# car.net
KiCad netlist of a schematic drawn in Altium Designer
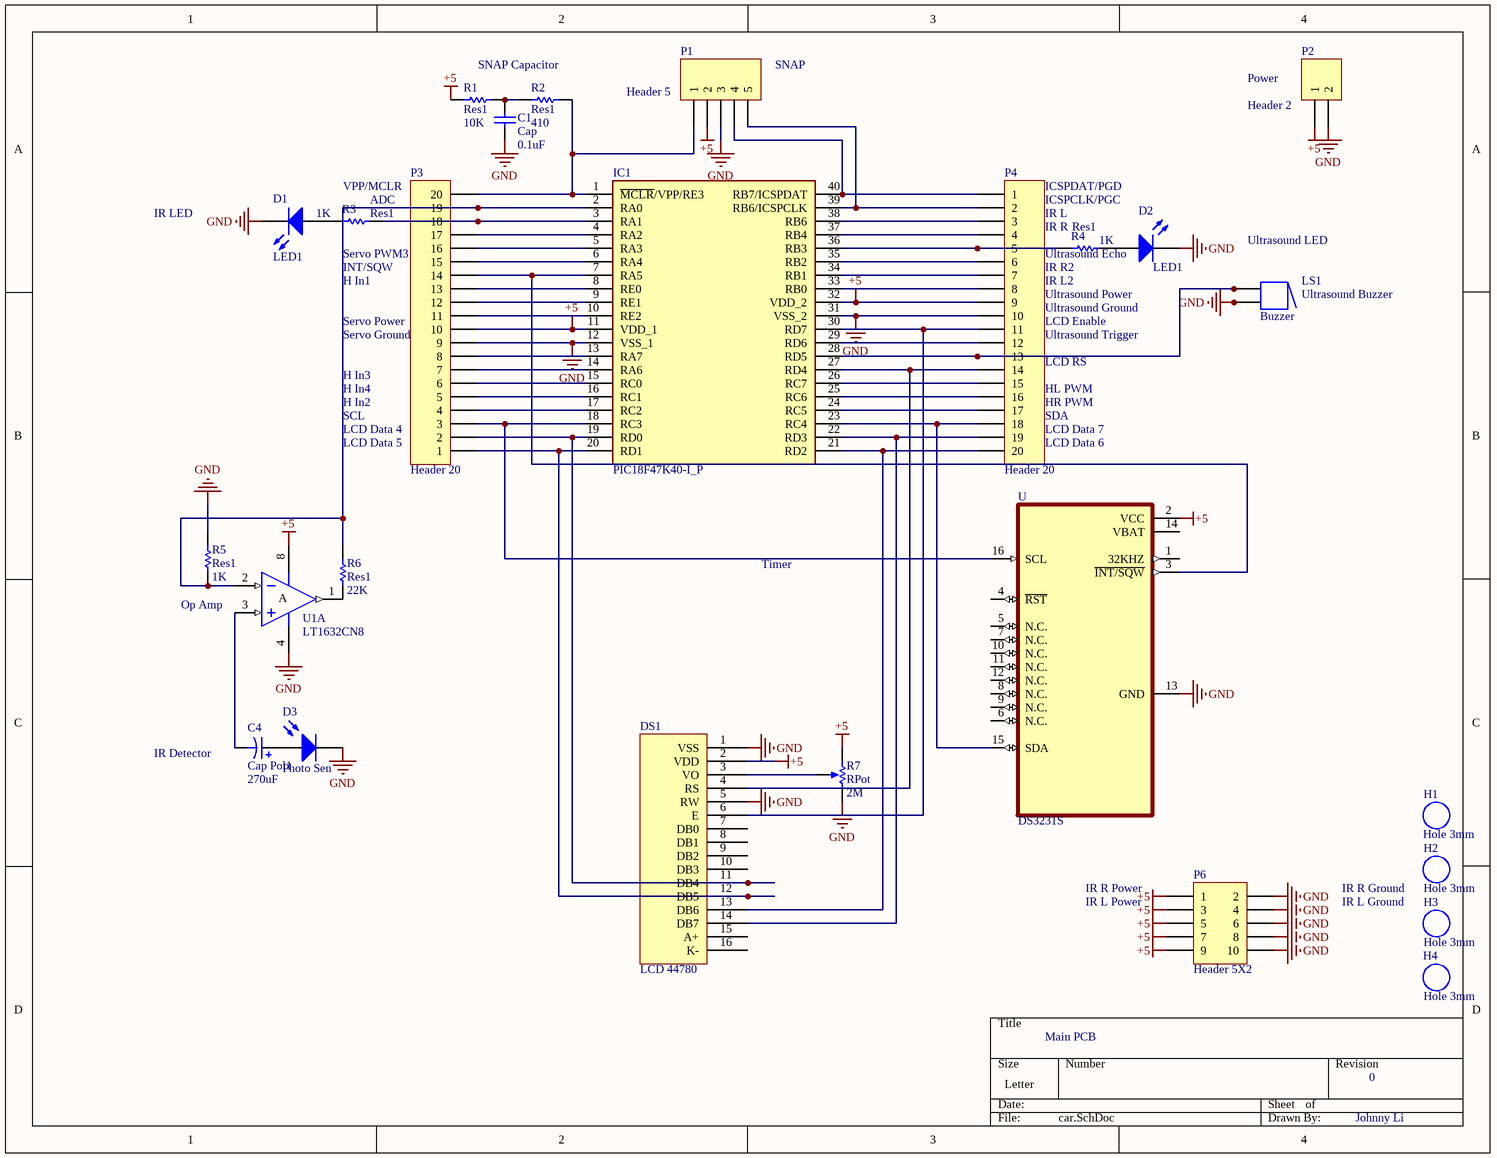
[diagram p0: car.SchDoc]

(export (version "E")
  (design (tool "Eeschema 10.0.6"))
  (components
    (comp (ref "C1")
      (value "Cap")
      (footprint "RAD-0.3")
      (description "Capacitor")
      (fields (field (name "ALTIUM_VALUE") "0.1uF") (field (name "PUBLISHER") "Altium Limited"))
      (libsource (lib "Miscellaneous Devices") (part "Cap"))
    )
    (comp (ref "C4")
      (value "Cap Pol1")
      (footprint "RAD-0.2")
      (description "Polarized Capacitor (Radial)")
      (fields (field (name "ALTIUM_VALUE") "270uF") (field (name "PUBLISHER") "Altium Limited"))
      (libsource (lib "Miscellaneous Devices") (part "Cap Pol1"))
    )
    (comp (ref "D1")
      (value "LED1")
      (footprint "LED-1")
      (description "Typical RED GaAs LED")
      (fields (field (name "PUBLISHER") "Altium Limited"))
      (libsource (lib "Miscellaneous Devices") (part "LED1"))
    )
    (comp (ref "D2")
      (value "LED1")
      (footprint "LED-1")
      (description "Typical RED GaAs LED")
      (fields (field (name "PUBLISHER") "Altium Limited"))
      (libsource (lib "Miscellaneous Devices") (part "LED1"))
    )
    (comp (ref "D3")
      (value "Photo Sen")
      (footprint "PIN2")
      (description "Photosensitive Diode")
      (fields (field (name "PUBLISHER") "Altium Limited"))
      (libsource (lib "Miscellaneous Devices") (part "Photo Sen"))
    )
    (comp (ref "DS1")
      (value "LCD 44780")
      (footprint "OLED 16x2")
      (libsource (lib "ECE LIB new") (part "LCD 44780"))
    )
    (comp (ref "H1")
      (value "Hole 3mm")
      (footprint "Hole 3mm")
      (libsource (lib "ECE LIB new") (part "Hole 3mm"))
    )
    (comp (ref "H2")
      (value "Hole 3mm")
      (footprint "Hole 3mm")
      (libsource (lib "ECE LIB new") (part "Hole 3mm"))
    )
    (comp (ref "H3")
      (value "Hole 3mm")
      (footprint "Hole 3mm")
      (libsource (lib "ECE LIB new") (part "Hole 3mm"))
    )
    (comp (ref "H4")
      (value "Hole 3mm")
      (footprint "Hole 3mm")
      (libsource (lib "ECE LIB new") (part "Hole 3mm"))
    )
    (comp (ref "IC1")
      (value "PIC18F47K40-I_P")
      (footprint "SamacSys:DIP1543W58P254L5175H635Q40N")
      (description "Integrated Circuit")
      (fields
        (field (name "MANUFACTURER_PART_NUMBER") "PIC18F47K40-I/P")
        (field (name "MOUSER PART NUMBER") "579-PIC18F47K40-I/P")
      )
      (libsource (lib "*") (part "PIC18F47K40-I_P"))
    )
    (comp (ref "LS1")
      (value "Buzzer")
      (footprint "ABSM-1574")
      (description "Magnetic Transducer Buzzer")
      (fields (field (name "PUBLISHER") "Altium Limited"))
      (libsource (lib "Miscellaneous Devices") (part "Buzzer"))
    )
    (comp (ref "P1")
      (value "Header 5")
      (footprint "HDR1X5")
      (description "Header, 5-Pin")
      (fields (field (name "PUBLISHER") "Altium Limited"))
      (libsource (lib "Miscellaneous Connectors") (part "Header 5"))
    )
    (comp (ref "P2")
      (value "Header 2")
      (footprint "HDR1X2")
      (description "Header, 2-Pin")
      (fields (field (name "PUBLISHER") "Altium Limited"))
      (libsource (lib "Miscellaneous Connectors") (part "Header 2"))
    )
    (comp (ref "P3")
      (value "Header 20")
      (footprint "HDR1X20")
      (description "Header, 20-Pin")
      (fields (field (name "PUBLISHER") "Altium Limited"))
      (libsource (lib "Miscellaneous Connectors") (part "Header 20"))
    )
    (comp (ref "P4")
      (value "Header 20")
      (footprint "HDR1X20")
      (description "Header, 20-Pin")
      (fields (field (name "PUBLISHER") "Altium Limited"))
      (libsource (lib "") (part "Header 20_1"))
    )
    (comp (ref "P6")
      (value "Header 5X2")
      (footprint "HDR2X5")
      (description "Header, 5-Pin, Dual row")
      (fields (field (name "PUBLISHER") "Altium Limited"))
      (libsource (lib "Miscellaneous Connectors") (part "Header 5X2"))
    )
    (comp (ref "R1")
      (value "Res1")
      (footprint "AXIAL-0.3")
      (description "Resistor")
      (fields (field (name "ALTIUM_VALUE") "10K") (field (name "PUBLISHER") "Altium Limited"))
      (libsource (lib "Miscellaneous Devices") (part "Res1"))
    )
    (comp (ref "R2")
      (value "Res1")
      (footprint "AXIAL-0.3")
      (description "Resistor")
      (fields (field (name "ALTIUM_VALUE") "410") (field (name "PUBLISHER") "Altium Limited"))
      (libsource (lib "Miscellaneous Devices") (part "Res1"))
    )
    (comp (ref "R3")
      (value "Res1")
      (footprint "AXIAL-0.3")
      (description "Resistor")
      (fields (field (name "ALTIUM_VALUE") "1K") (field (name "PUBLISHER") "Altium Limited"))
      (libsource (lib "Miscellaneous Devices") (part "Res1"))
    )
    (comp (ref "R4")
      (value "Res1")
      (footprint "AXIAL-0.3")
      (description "Resistor")
      (fields (field (name "ALTIUM_VALUE") "1K") (field (name "PUBLISHER") "Altium Limited"))
      (libsource (lib "Miscellaneous Devices") (part "Res1"))
    )
    (comp (ref "R5")
      (value "Res1")
      (footprint "AXIAL-0.3")
      (description "Resistor")
      (fields (field (name "ALTIUM_VALUE") "1K") (field (name "PUBLISHER") "Altium Limited"))
      (libsource (lib "Miscellaneous Devices") (part "Res1"))
    )
    (comp (ref "R6")
      (value "Res1")
      (footprint "AXIAL-0.3")
      (description "Resistor")
      (fields (field (name "ALTIUM_VALUE") "22K") (field (name "PUBLISHER") "Altium Limited"))
      (libsource (lib "Miscellaneous Devices") (part "Res1"))
    )
    (comp (ref "R7")
      (value "RPot")
      (footprint "VR5")
      (description "Potentiometer")
      (fields (field (name "ALTIUM_VALUE") "2M") (field (name "PUBLISHER") "Altium Limited"))
      (libsource (lib "Miscellaneous Devices") (part "RPot"))
    )
    (comp (ref "U")
      (value "DS3231S")
      (footprint "SOIC127P1032X265-16N")
      (description "Real Time Clock _RTC_ IC Clock/Calendar IÂ²C, 2-Wire Serial 16-SOIC _0.295, 7.50mm Width_")
      (fields (field (name "MF") "Maxim Integrated"))
      (libsource (lib "DS3231S") (part "DS3231S"))
    )
    (comp (ref "U1")
      (value "LT1632CN8")
      (footprint "DIP-8")
      (description "45MHz, 45V/µs, Dual Rail-to-Rail Input and Output Precision Operational Amplifier")
      (fields (field (name "PUBLISHER") "Altium Limited"))
      (libsource (lib "ECE LIB new") (part "LT1632CN8"))
    )
  )
  (nets
    (net (code "1") (name "+5") (class "Default")
      (node (ref "DS1") (pin "2") (pinfunction "VDD_2") (pintype "passive"))
      (node (ref "IC1") (pin "11") (pinfunction "VDD_1_11") (pintype "passive"))
      (node (ref "IC1") (pin "32") (pinfunction "VDD_2_32") (pintype "passive"))
      (node (ref "P1") (pin "2") (pinfunction "2_2") (pintype "passive"))
      (node (ref "P2") (pin "1") (pinfunction "1_1") (pintype "passive"))
      (node (ref "P3") (pin "10") (pinfunction "10_10") (pintype "passive"))
      (node (ref "P4") (pin "9") (pinfunction "9_9") (pintype "passive"))
      (node (ref "P6") (pin "1") (pinfunction "1_1") (pintype "passive"))
      (node (ref "P6") (pin "3") (pinfunction "3_3") (pintype "passive"))
      (node (ref "P6") (pin "5") (pinfunction "5_5") (pintype "passive"))
      (node (ref "P6") (pin "7") (pinfunction "7_7") (pintype "passive"))
      (node (ref "P6") (pin "9") (pinfunction "9_9") (pintype "passive"))
      (node (ref "R1") (pin "1") (pinfunction "1_1") (pintype "passive"))
      (node (ref "R7") (pin "1") (pinfunction "TOP_1") (pintype "passive"))
      (node (ref "U") (pin "2") (pinfunction "VCC_2") (pintype "power_in"))
      (node (ref "U1") (pin "8") (pinfunction "V+_8") (pintype "power_in"))
    )
    (net (code "2") (name "GND") (class "Default")
      (node (ref "C1") (pin "1") (pinfunction "1_1") (pintype "passive"))
      (node (ref "D1") (pin "2") (pinfunction "K_2") (pintype "passive"))
      (node (ref "D2") (pin "2") (pinfunction "K_2") (pintype "passive"))
      (node (ref "D3") (pin "2") (pinfunction "K_2") (pintype "passive"))
      (node (ref "DS1") (pin "1") (pinfunction "VSS_1") (pintype "passive"))
      (node (ref "DS1") (pin "5") (pinfunction "RW_5") (pintype "passive"))
      (node (ref "IC1") (pin "12") (pinfunction "VSS_1_12") (pintype "passive"))
      (node (ref "IC1") (pin "31") (pinfunction "VSS_2_31") (pintype "passive"))
      (node (ref "LS1") (pin "2") (pinfunction "2_2") (pintype "passive"))
      (node (ref "LS1") (pin "2A") (pinfunction "2A_2A") (pintype "passive"))
      (node (ref "P1") (pin "3") (pinfunction "3_3") (pintype "passive"))
      (node (ref "P2") (pin "2") (pinfunction "2_2") (pintype "passive"))
      (node (ref "P3") (pin "9") (pinfunction "9_9") (pintype "passive"))
      (node (ref "P4") (pin "10") (pinfunction "10_10") (pintype "passive"))
      (node (ref "P6") (pin "10") (pinfunction "10_10") (pintype "passive"))
      (node (ref "P6") (pin "2") (pinfunction "2_2") (pintype "passive"))
      (node (ref "P6") (pin "4") (pinfunction "4_4") (pintype "passive"))
      (node (ref "P6") (pin "6") (pinfunction "6_6") (pintype "passive"))
      (node (ref "P6") (pin "8") (pinfunction "8_8") (pintype "passive"))
      (node (ref "R5") (pin "2") (pinfunction "2_2") (pintype "passive"))
      (node (ref "R7") (pin "2") (pinfunction "BOT_2") (pintype "passive"))
      (node (ref "U") (pin "13") (pinfunction "GND_13") (pintype "power_in"))
      (node (ref "U1") (pin "4") (pinfunction "V-_4") (pintype "power_in"))
    )
    (net (code "3") (name "Net-(C1-Pad2)") (class "Default")
      (node (ref "C1") (pin "2") (pinfunction "2_2") (pintype "passive"))
      (node (ref "R1") (pin "2") (pinfunction "2_2") (pintype "passive"))
      (node (ref "R2") (pin "1") (pinfunction "1_1") (pintype "passive"))
    )
    (net (code "4") (name "Net-(D1-A)") (class "Default")
      (node (ref "D1") (pin "1") (pinfunction "A_1") (pintype "passive"))
      (node (ref "R3") (pin "2") (pinfunction "2_2") (pintype "passive"))
    )
    (net (code "5") (name "Net-(D2-A)") (class "Default")
      (node (ref "D2") (pin "1") (pinfunction "A_1") (pintype "passive"))
      (node (ref "R4") (pin "2") (pinfunction "2_2") (pintype "passive"))
    )
    (net (code "6") (name "Net-(D3-A)") (class "Default")
      (node (ref "C4") (pin "1") (pinfunction "1_1") (pintype "passive"))
      (node (ref "D3") (pin "1") (pinfunction "A_1") (pintype "passive"))
    )
    (net (code "7") (name "Net-(DS1-DB4)") (class "Default")
      (node (ref "DS1") (pin "11") (pinfunction "DB4_11") (pintype "passive"))
      (node (ref "IC1") (pin "19") (pinfunction "RD0_19") (pintype "passive"))
      (node (ref "P3") (pin "2") (pinfunction "2_2") (pintype "passive"))
    )
    (net (code "8") (name "Net-(DS1-DB5)") (class "Default")
      (node (ref "DS1") (pin "12") (pinfunction "DB5_12") (pintype "passive"))
      (node (ref "IC1") (pin "20") (pinfunction "RD1_20") (pintype "passive"))
      (node (ref "P3") (pin "1") (pinfunction "1_1") (pintype "passive"))
    )
    (net (code "9") (name "Net-(DS1-DB6)") (class "Default")
      (node (ref "DS1") (pin "13") (pinfunction "DB6_13") (pintype "passive"))
      (node (ref "IC1") (pin "21") (pinfunction "RD2_21") (pintype "passive"))
      (node (ref "P4") (pin "20") (pinfunction "20_20") (pintype "passive"))
    )
    (net (code "10") (name "Net-(DS1-DB7)") (class "Default")
      (node (ref "DS1") (pin "14") (pinfunction "DB7_14") (pintype "passive"))
      (node (ref "IC1") (pin "22") (pinfunction "RD3_22") (pintype "passive"))
      (node (ref "P4") (pin "19") (pinfunction "19_19") (pintype "passive"))
    )
    (net (code "11") (name "Net-(DS1-E)") (class "Default")
      (node (ref "DS1") (pin "6") (pinfunction "E_6") (pintype "passive"))
      (node (ref "IC1") (pin "30") (pinfunction "RD7_30") (pintype "passive"))
      (node (ref "P4") (pin "11") (pinfunction "11_11") (pintype "passive"))
    )
    (net (code "12") (name "Net-(DS1-RS)") (class "Default")
      (node (ref "DS1") (pin "4") (pinfunction "RS_4") (pintype "passive"))
      (node (ref "IC1") (pin "27") (pinfunction "RD4_27") (pintype "passive"))
      (node (ref "P4") (pin "14") (pinfunction "14_14") (pintype "passive"))
    )
    (net (code "13") (name "Net-(DS1-VO)") (class "Default")
      (node (ref "DS1") (pin "3") (pinfunction "VO_3") (pintype "passive"))
      (node (ref "R7") (pin "3") (pinfunction "TAP_3") (pintype "passive"))
    )
    (net (code "14") (name "Net-(IC1-RA0)") (class "Default")
      (node (ref "IC1") (pin "2") (pinfunction "RA0_2") (pintype "passive"))
      (node (ref "P3") (pin "19") (pinfunction "19_19") (pintype "passive"))
      (node (ref "R5") (pin "1") (pinfunction "1_1") (pintype "passive"))
      (node (ref "R6") (pin "2") (pinfunction "2_2") (pintype "passive"))
      (node (ref "U1") (pin "2") (pinfunction "IN-_2") (pintype "input"))
    )
    (net (code "15") (name "Net-(IC1-RA1)") (class "Default")
      (node (ref "IC1") (pin "3") (pinfunction "RA1_3") (pintype "passive"))
      (node (ref "P3") (pin "18") (pinfunction "18_18") (pintype "passive"))
      (node (ref "R3") (pin "1") (pinfunction "1_1") (pintype "passive"))
    )
    (net (code "16") (name "Net-(IC1-RA2)") (class "Default")
      (node (ref "IC1") (pin "4") (pinfunction "RA2_4") (pintype "passive"))
      (node (ref "P3") (pin "17") (pinfunction "17_17") (pintype "passive"))
    )
    (net (code "17") (name "Net-(IC1-RA3)") (class "Default")
      (node (ref "IC1") (pin "5") (pinfunction "RA3_5") (pintype "passive"))
      (node (ref "P3") (pin "16") (pinfunction "16_16") (pintype "passive"))
    )
    (net (code "18") (name "Net-(IC1-RA4)") (class "Default")
      (node (ref "IC1") (pin "6") (pinfunction "RA4_6") (pintype "passive"))
      (node (ref "P3") (pin "15") (pinfunction "15_15") (pintype "passive"))
    )
    (net (code "19") (name "Net-(IC1-RA5)") (class "Default")
      (node (ref "IC1") (pin "7") (pinfunction "RA5_7") (pintype "passive"))
      (node (ref "P3") (pin "14") (pinfunction "14_14") (pintype "passive"))
      (node (ref "U") (pin "3") (pinfunction "~{INT/SQW}_3") (pintype "output"))
    )
    (net (code "20") (name "Net-(IC1-RA6)") (class "Default")
      (node (ref "IC1") (pin "14") (pinfunction "RA6_14") (pintype "passive"))
      (node (ref "P3") (pin "7") (pinfunction "7_7") (pintype "passive"))
    )
    (net (code "21") (name "Net-(IC1-RA7)") (class "Default")
      (node (ref "IC1") (pin "13") (pinfunction "RA7_13") (pintype "passive"))
      (node (ref "P3") (pin "8") (pinfunction "8_8") (pintype "passive"))
    )
    (net (code "22") (name "Net-(IC1-RB0)") (class "Default")
      (node (ref "IC1") (pin "33") (pinfunction "RB0_33") (pintype "passive"))
      (node (ref "P4") (pin "8") (pinfunction "8_8") (pintype "passive"))
    )
    (net (code "23") (name "Net-(IC1-RB1)") (class "Default")
      (node (ref "IC1") (pin "34") (pinfunction "RB1_34") (pintype "passive"))
      (node (ref "P4") (pin "7") (pinfunction "7_7") (pintype "passive"))
    )
    (net (code "24") (name "Net-(IC1-RB2)") (class "Default")
      (node (ref "IC1") (pin "35") (pinfunction "RB2_35") (pintype "passive"))
      (node (ref "P4") (pin "6") (pinfunction "6_6") (pintype "passive"))
    )
    (net (code "25") (name "Net-(IC1-RB3)") (class "Default")
      (node (ref "IC1") (pin "36") (pinfunction "RB3_36") (pintype "passive"))
      (node (ref "P4") (pin "5") (pinfunction "5_5") (pintype "passive"))
      (node (ref "R4") (pin "1") (pinfunction "1_1") (pintype "passive"))
    )
    (net (code "26") (name "Net-(IC1-RB4)") (class "Default")
      (node (ref "IC1") (pin "37") (pinfunction "RB4_37") (pintype "passive"))
      (node (ref "P4") (pin "4") (pinfunction "4_4") (pintype "passive"))
    )
    (net (code "27") (name "Net-(IC1-RB6)") (class "Default")
      (node (ref "IC1") (pin "38") (pinfunction "RB6_38") (pintype "passive"))
      (node (ref "P4") (pin "3") (pinfunction "3_3") (pintype "passive"))
    )
    (net (code "28") (name "Net-(IC1-RB6{slash}ICSPCLK)") (class "Default")
      (node (ref "IC1") (pin "39") (pinfunction "RB6/ICSPCLK_39") (pintype "passive"))
      (node (ref "P1") (pin "5") (pinfunction "5_5") (pintype "passive"))
      (node (ref "P4") (pin "2") (pinfunction "2_2") (pintype "passive"))
    )
    (net (code "29") (name "Net-(IC1-RB7{slash}ICSPDAT)") (class "Default")
      (node (ref "IC1") (pin "40") (pinfunction "RB7/ICSPDAT_40") (pintype "passive"))
      (node (ref "P1") (pin "4") (pinfunction "4_4") (pintype "passive"))
      (node (ref "P4") (pin "1") (pinfunction "1_1") (pintype "passive"))
    )
    (net (code "30") (name "Net-(IC1-RC0)") (class "Default")
      (node (ref "IC1") (pin "15") (pinfunction "RC0_15") (pintype "passive"))
      (node (ref "P3") (pin "6") (pinfunction "6_6") (pintype "passive"))
    )
    (net (code "31") (name "Net-(IC1-RC1)") (class "Default")
      (node (ref "IC1") (pin "16") (pinfunction "RC1_16") (pintype "passive"))
      (node (ref "P3") (pin "5") (pinfunction "5_5") (pintype "passive"))
    )
    (net (code "32") (name "Net-(IC1-RC2)") (class "Default")
      (node (ref "IC1") (pin "17") (pinfunction "RC2_17") (pintype "passive"))
      (node (ref "P3") (pin "4") (pinfunction "4_4") (pintype "passive"))
    )
    (net (code "33") (name "Net-(IC1-RC3)") (class "Default")
      (node (ref "IC1") (pin "18") (pinfunction "RC3_18") (pintype "passive"))
      (node (ref "P3") (pin "3") (pinfunction "3_3") (pintype "passive"))
      (node (ref "U") (pin "16") (pinfunction "SCL_16") (pintype "input"))
    )
    (net (code "34") (name "Net-(IC1-RC4)") (class "Default")
      (node (ref "IC1") (pin "23") (pinfunction "RC4_23") (pintype "passive"))
      (node (ref "P4") (pin "18") (pinfunction "18_18") (pintype "passive"))
      (node (ref "U") (pin "15") (pinfunction "SDA_15") (pintype "bidirectional"))
    )
    (net (code "35") (name "Net-(IC1-RC5)") (class "Default")
      (node (ref "IC1") (pin "24") (pinfunction "RC5_24") (pintype "passive"))
      (node (ref "P4") (pin "17") (pinfunction "17_17") (pintype "passive"))
    )
    (net (code "36") (name "Net-(IC1-RC6)") (class "Default")
      (node (ref "IC1") (pin "25") (pinfunction "RC6_25") (pintype "passive"))
      (node (ref "P4") (pin "16") (pinfunction "16_16") (pintype "passive"))
    )
    (net (code "37") (name "Net-(IC1-RC7)") (class "Default")
      (node (ref "IC1") (pin "26") (pinfunction "RC7_26") (pintype "passive"))
      (node (ref "P4") (pin "15") (pinfunction "15_15") (pintype "passive"))
    )
    (net (code "38") (name "Net-(IC1-RD5)") (class "Default")
      (node (ref "IC1") (pin "28") (pinfunction "RD5_28") (pintype "passive"))
      (node (ref "LS1") (pin "1") (pinfunction "1_1") (pintype "passive"))
      (node (ref "LS1") (pin "1A") (pinfunction "1A_1A") (pintype "passive"))
      (node (ref "P4") (pin "13") (pinfunction "13_13") (pintype "passive"))
    )
    (net (code "39") (name "Net-(IC1-RD6)") (class "Default")
      (node (ref "IC1") (pin "29") (pinfunction "RD6_29") (pintype "passive"))
      (node (ref "P4") (pin "12") (pinfunction "12_12") (pintype "passive"))
    )
    (net (code "40") (name "Net-(IC1-RE0)") (class "Default")
      (node (ref "IC1") (pin "8") (pinfunction "RE0_8") (pintype "passive"))
      (node (ref "P3") (pin "13") (pinfunction "13_13") (pintype "passive"))
    )
    (net (code "41") (name "Net-(IC1-RE1)") (class "Default")
      (node (ref "IC1") (pin "9") (pinfunction "RE1_9") (pintype "passive"))
      (node (ref "P3") (pin "12") (pinfunction "12_12") (pintype "passive"))
    )
    (net (code "42") (name "Net-(IC1-RE2)") (class "Default")
      (node (ref "IC1") (pin "10") (pinfunction "RE2_10") (pintype "passive"))
      (node (ref "P3") (pin "11") (pinfunction "11_11") (pintype "passive"))
    )
    (net (code "43") (name "Net-(IC1-~{MCLR}{slash}VPP{slash}RE3)") (class "Default")
      (node (ref "IC1") (pin "1") (pinfunction "~{MCLR}/VPP/RE3_1") (pintype "passive"))
      (node (ref "P1") (pin "1") (pinfunction "1_1") (pintype "passive"))
      (node (ref "P3") (pin "20") (pinfunction "20_20") (pintype "passive"))
      (node (ref "R2") (pin "2") (pinfunction "2_2") (pintype "passive"))
    )
    (net (code "44") (name "Net-(U1A-IN+)") (class "Default")
      (node (ref "C4") (pin "2") (pinfunction "2_2") (pintype "passive"))
      (node (ref "U1") (pin "3") (pinfunction "IN+_3") (pintype "input"))
    )
    (net (code "45") (name "Net-(U1A-OUT)") (class "Default")
      (node (ref "R6") (pin "1") (pinfunction "1_1") (pintype "passive"))
      (node (ref "U1") (pin "1") (pinfunction "OUT_1") (pintype "output"))
    )
    (net (code "46") (name "unconnected-(DS1-A+-Pad15)") (class "Default")
      (node (ref "DS1") (pin "15") (pinfunction "A+_15") (pintype "passive"))
    )
    (net (code "47") (name "unconnected-(DS1-DB0-Pad7)") (class "Default")
      (node (ref "DS1") (pin "7") (pinfunction "DB0_7") (pintype "passive"))
    )
    (net (code "48") (name "unconnected-(DS1-DB1-Pad8)") (class "Default")
      (node (ref "DS1") (pin "8") (pinfunction "DB1_8") (pintype "passive"))
    )
    (net (code "49") (name "unconnected-(DS1-DB2-Pad9)") (class "Default")
      (node (ref "DS1") (pin "9") (pinfunction "DB2_9") (pintype "passive"))
    )
    (net (code "50") (name "unconnected-(DS1-DB3-Pad10)") (class "Default")
      (node (ref "DS1") (pin "10") (pinfunction "DB3_10") (pintype "passive"))
    )
    (net (code "51") (name "unconnected-(DS1-K--Pad16)") (class "Default")
      (node (ref "DS1") (pin "16") (pinfunction "K-_16") (pintype "passive"))
    )
    (net (code "52") (name "unconnected-(U-32KHZ-Pad1)") (class "Default")
      (node (ref "U") (pin "1") (pinfunction "32KHZ_1") (pintype "output"))
    )
    (net (code "53") (name "unconnected-(U-N.C.-Pad5)") (class "Default")
      (node (ref "U") (pin "5") (pinfunction "N.C._5") (pintype "bidirectional"))
    )
    (net (code "54") (name "unconnected-(U-N.C.-Pad6)") (class "Default")
      (node (ref "U") (pin "6") (pinfunction "N.C._6") (pintype "bidirectional"))
    )
    (net (code "55") (name "unconnected-(U-N.C.-Pad7)") (class "Default")
      (node (ref "U") (pin "7") (pinfunction "N.C._7") (pintype "bidirectional"))
    )
    (net (code "56") (name "unconnected-(U-N.C.-Pad8)") (class "Default")
      (node (ref "U") (pin "8") (pinfunction "N.C._8") (pintype "bidirectional"))
    )
    (net (code "57") (name "unconnected-(U-N.C.-Pad9)") (class "Default")
      (node (ref "U") (pin "9") (pinfunction "N.C._9") (pintype "bidirectional"))
    )
    (net (code "58") (name "unconnected-(U-N.C.-Pad10)") (class "Default")
      (node (ref "U") (pin "10") (pinfunction "N.C._10") (pintype "bidirectional"))
    )
    (net (code "59") (name "unconnected-(U-N.C.-Pad11)") (class "Default")
      (node (ref "U") (pin "11") (pinfunction "N.C._11") (pintype "bidirectional"))
    )
    (net (code "60") (name "unconnected-(U-N.C.-Pad12)") (class "Default")
      (node (ref "U") (pin "12") (pinfunction "N.C._12") (pintype "bidirectional"))
    )
    (net (code "61") (name "unconnected-(U-VBAT-Pad14)") (class "Default")
      (node (ref "U") (pin "14") (pinfunction "VBAT_14") (pintype "power_in"))
    )
    (net (code "62") (name "unconnected-(U-~{RST}-Pad4)") (class "Default")
      (node (ref "U") (pin "4") (pinfunction "~{RST}_4") (pintype "bidirectional"))
    )
  )
)
